# HoneywellPressurePCB.net
KiCad netlist of a schematic drawn in EAGLE
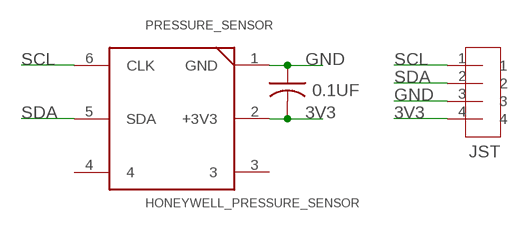
[diagram p0: schematic, sheet 1]

(export (version "E")
  (design (tool "Eeschema 10.0.6"))
  (components
    (comp (ref "0.1UF")
      (value "C-USC1206")
      (footprint "eagle-import:C1206")
      (libsource (lib "eagle-import") (part "C-USC1206"))
    )
    (comp (ref "JST")
      (value "2.5MM_JST_UP_4POS")
      (footprint "eagle-import:JST_4POS_2.5MM_UP")
      (libsource (lib "eagle-import") (part "2.5MM_JST_UP_4POS"))
    )
    (comp (ref "PRESSURE_SENSOR")
      (value "HONEYWELL_PRESSURE_SENSOR")
      (footprint "eagle-import:DIP6")
      (libsource (lib "eagle-import") (part "HONEYWELL_PRESSURE_SENSOR"))
    )
  )
  (nets
    (net (code "1") (name "/3V3") (class "Default")
      (node (ref "0.1UF") (pin "2") (pinfunction "2_2") (pintype "passive"))
      (node (ref "JST") (pin "4") (pinfunction "4_4") (pintype "bidirectional"))
      (node (ref "PRESSURE_SENSOR") (pin "2") (pinfunction "+3V3_2") (pintype "bidirectional"))
    )
    (net (code "2") (name "/GND") (class "Default")
      (node (ref "0.1UF") (pin "1") (pinfunction "1_1") (pintype "passive"))
      (node (ref "JST") (pin "3") (pinfunction "3_3") (pintype "bidirectional"))
      (node (ref "PRESSURE_SENSOR") (pin "1") (pinfunction "GND_1") (pintype "bidirectional"))
    )
    (net (code "3") (name "/SCL") (class "Default")
      (node (ref "JST") (pin "1") (pinfunction "1_1") (pintype "bidirectional"))
      (node (ref "PRESSURE_SENSOR") (pin "6") (pinfunction "CLK_6") (pintype "bidirectional"))
    )
    (net (code "4") (name "/SDA") (class "Default")
      (node (ref "JST") (pin "2") (pinfunction "2_2") (pintype "bidirectional"))
      (node (ref "PRESSURE_SENSOR") (pin "5") (pinfunction "SDA_5") (pintype "bidirectional"))
    )
    (net (code "5") (name "unconnected-(PRESSURE_SENSOR-Pad3)") (class "Default")
      (node (ref "PRESSURE_SENSOR") (pin "3") (pinfunction "3_3") (pintype "bidirectional"))
    )
    (net (code "6") (name "unconnected-(PRESSURE_SENSOR-Pad4)") (class "Default")
      (node (ref "PRESSURE_SENSOR") (pin "4") (pinfunction "4_4") (pintype "bidirectional"))
    )
  )
)
